# PortExpanderXRA1207_v2.net
KiCad netlist of a schematic drawn in EAGLE
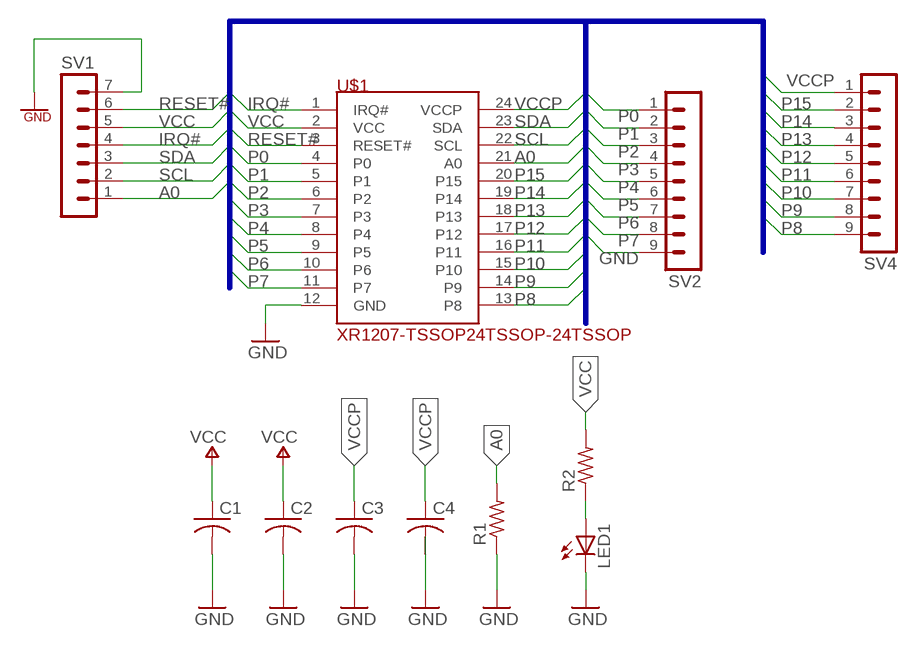
[diagram p0: schematic, sheet 1]

(export (version "E")
  (design (tool "Eeschema 10.0.6"))
  (components
    (comp (ref "C1")
      (value "C-USC1206")
      (footprint "eagle-import:C1206")
      (libsource (lib "eagle-import") (part "C-USC1206"))
    )
    (comp (ref "C2")
      (value "C-USC1206")
      (footprint "eagle-import:C1206")
      (libsource (lib "eagle-import") (part "C-USC1206"))
    )
    (comp (ref "C3")
      (value "C-USC1206")
      (footprint "eagle-import:C1206")
      (libsource (lib "eagle-import") (part "C-USC1206"))
    )
    (comp (ref "C4")
      (value "C-USC1206")
      (footprint "eagle-import:C1206")
      (libsource (lib "eagle-import") (part "C-USC1206"))
    )
    (comp (ref "LED1")
      (value "LEDSML0805")
      (footprint "eagle-import:SML0805")
      (libsource (lib "eagle-import") (part "LEDSML0805"))
    )
    (comp (ref "R1")
      (value "R-US_M1206")
      (footprint "eagle-import:M1206")
      (libsource (lib "eagle-import") (part "R-US_M1206"))
    )
    (comp (ref "R2")
      (value "R-US_M1206")
      (footprint "eagle-import:M1206")
      (libsource (lib "eagle-import") (part "R-US_M1206"))
    )
    (comp (ref "SV1")
      (value "MA07-1")
      (footprint "eagle-import:MA07-1")
      (libsource (lib "eagle-import") (part "MA07-1"))
    )
    (comp (ref "SV2")
      (value "MA09-1")
      (footprint "eagle-import:MA09-1")
      (libsource (lib "eagle-import") (part "MA09-1"))
    )
    (comp (ref "SV4")
      (value "MA09-1")
      (footprint "eagle-import:MA09-1")
      (libsource (lib "eagle-import") (part "MA09-1"))
    )
    (comp (ref "U$1")
      (value "XR1207-TSSOP24TSSOP-24TSSOP")
      (footprint "eagle-import:TSSOP-24")
      (libsource (lib "eagle-import") (part "XR1207-TSSOP24TSSOPTSSOP-24"))
    )
  )
  (nets
    (net (code "1") (name "/IRQ#") (class "Default")
      (node (ref "SV1") (pin "4") (pinfunction "4_4") (pintype "passive"))
      (node (ref "U$1") (pin "1") (pinfunction "IRQ#_1") (pintype "bidirectional"))
    )
    (net (code "2") (name "/P0") (class "Default")
      (node (ref "SV2") (pin "1") (pinfunction "1_1") (pintype "passive"))
      (node (ref "U$1") (pin "4") (pinfunction "P0_4") (pintype "bidirectional"))
    )
    (net (code "3") (name "/P1") (class "Default")
      (node (ref "SV2") (pin "2") (pinfunction "2_2") (pintype "passive"))
      (node (ref "U$1") (pin "5") (pinfunction "P1_5") (pintype "bidirectional"))
    )
    (net (code "4") (name "/P2") (class "Default")
      (node (ref "SV2") (pin "3") (pinfunction "3_3") (pintype "passive"))
      (node (ref "U$1") (pin "6") (pinfunction "P2_6") (pintype "bidirectional"))
    )
    (net (code "5") (name "/P3") (class "Default")
      (node (ref "SV2") (pin "4") (pinfunction "4_4") (pintype "passive"))
      (node (ref "U$1") (pin "7") (pinfunction "P3_7") (pintype "bidirectional"))
    )
    (net (code "6") (name "/P4") (class "Default")
      (node (ref "SV2") (pin "5") (pinfunction "5_5") (pintype "passive"))
      (node (ref "U$1") (pin "8") (pinfunction "P4_8") (pintype "bidirectional"))
    )
    (net (code "7") (name "/P5") (class "Default")
      (node (ref "SV2") (pin "6") (pinfunction "6_6") (pintype "passive"))
      (node (ref "U$1") (pin "9") (pinfunction "P5_9") (pintype "bidirectional"))
    )
    (net (code "8") (name "/P6") (class "Default")
      (node (ref "SV2") (pin "7") (pinfunction "7_7") (pintype "passive"))
      (node (ref "U$1") (pin "10") (pinfunction "P6_10") (pintype "bidirectional"))
    )
    (net (code "9") (name "/P7") (class "Default")
      (node (ref "SV2") (pin "8") (pinfunction "8_8") (pintype "passive"))
      (node (ref "U$1") (pin "11") (pinfunction "P7_11") (pintype "bidirectional"))
    )
    (net (code "10") (name "/P8") (class "Default")
      (node (ref "SV4") (pin "9") (pinfunction "9_9") (pintype "passive"))
      (node (ref "U$1") (pin "13") (pinfunction "P8_13") (pintype "bidirectional"))
    )
    (net (code "11") (name "/P9") (class "Default")
      (node (ref "SV4") (pin "8") (pinfunction "8_8") (pintype "passive"))
      (node (ref "U$1") (pin "14") (pinfunction "P9_14") (pintype "bidirectional"))
    )
    (net (code "12") (name "/P10") (class "Default")
      (node (ref "SV4") (pin "7") (pinfunction "7_7") (pintype "passive"))
      (node (ref "U$1") (pin "15") (pinfunction "P10_15") (pintype "bidirectional"))
    )
    (net (code "13") (name "/P11") (class "Default")
      (node (ref "SV4") (pin "6") (pinfunction "6_6") (pintype "passive"))
      (node (ref "U$1") (pin "16") (pinfunction "P11_16") (pintype "bidirectional"))
    )
    (net (code "14") (name "/P12") (class "Default")
      (node (ref "SV4") (pin "5") (pinfunction "5_5") (pintype "passive"))
      (node (ref "U$1") (pin "17") (pinfunction "P12_17") (pintype "bidirectional"))
    )
    (net (code "15") (name "/P13") (class "Default")
      (node (ref "SV4") (pin "4") (pinfunction "4_4") (pintype "passive"))
      (node (ref "U$1") (pin "18") (pinfunction "P13_18") (pintype "bidirectional"))
    )
    (net (code "16") (name "/P14") (class "Default")
      (node (ref "SV4") (pin "3") (pinfunction "3_3") (pintype "passive"))
      (node (ref "U$1") (pin "19") (pinfunction "P14_19") (pintype "bidirectional"))
    )
    (net (code "17") (name "/P15") (class "Default")
      (node (ref "SV4") (pin "2") (pinfunction "2_2") (pintype "passive"))
      (node (ref "U$1") (pin "20") (pinfunction "P15_20") (pintype "bidirectional"))
    )
    (net (code "18") (name "/RESET#") (class "Default")
      (node (ref "SV1") (pin "6") (pinfunction "6_6") (pintype "passive"))
      (node (ref "U$1") (pin "3") (pinfunction "RESET#_3") (pintype "bidirectional"))
    )
    (net (code "19") (name "/SCL") (class "Default")
      (node (ref "SV1") (pin "2") (pinfunction "2_2") (pintype "passive"))
      (node (ref "U$1") (pin "22") (pinfunction "SCL_22") (pintype "bidirectional"))
    )
    (net (code "20") (name "/SDA") (class "Default")
      (node (ref "SV1") (pin "3") (pinfunction "3_3") (pintype "passive"))
      (node (ref "U$1") (pin "23") (pinfunction "SDA_23") (pintype "bidirectional"))
    )
    (net (code "21") (name "A0") (class "Default")
      (node (ref "R1") (pin "2") (pinfunction "2_2") (pintype "passive"))
      (node (ref "SV1") (pin "1") (pinfunction "1_1") (pintype "passive"))
      (node (ref "U$1") (pin "21") (pinfunction "A0_21") (pintype "bidirectional"))
    )
    (net (code "22") (name "GND") (class "Default")
      (node (ref "C1") (pin "2") (pinfunction "2_2") (pintype "passive"))
      (node (ref "C2") (pin "2") (pinfunction "2_2") (pintype "passive"))
      (node (ref "C3") (pin "2") (pinfunction "2_2") (pintype "passive"))
      (node (ref "C4") (pin "2") (pinfunction "2_2") (pintype "passive"))
      (node (ref "LED1") (pin "C") (pinfunction "C_C") (pintype "passive"))
      (node (ref "R1") (pin "1") (pinfunction "1_1") (pintype "passive"))
      (node (ref "SV1") (pin "7") (pinfunction "7_7") (pintype "passive"))
      (node (ref "SV2") (pin "9") (pinfunction "9_9") (pintype "passive"))
      (node (ref "U$1") (pin "12") (pinfunction "GND_12") (pintype "bidirectional"))
    )
    (net (code "23") (name "Net-(LED1-PadA)") (class "Default")
      (node (ref "LED1") (pin "A") (pinfunction "A_A") (pintype "passive"))
      (node (ref "R2") (pin "1") (pinfunction "1_1") (pintype "passive"))
    )
    (net (code "24") (name "VCC") (class "Default")
      (node (ref "C1") (pin "1") (pinfunction "1_1") (pintype "passive"))
      (node (ref "C2") (pin "1") (pinfunction "1_1") (pintype "passive"))
      (node (ref "R2") (pin "2") (pinfunction "2_2") (pintype "passive"))
      (node (ref "SV1") (pin "5") (pinfunction "5_5") (pintype "passive"))
      (node (ref "U$1") (pin "2") (pinfunction "VCC_2") (pintype "bidirectional"))
    )
    (net (code "25") (name "VCCP") (class "Default")
      (node (ref "C3") (pin "1") (pinfunction "1_1") (pintype "passive"))
      (node (ref "C4") (pin "1") (pinfunction "1_1") (pintype "passive"))
      (node (ref "SV4") (pin "1") (pinfunction "1_1") (pintype "passive"))
      (node (ref "U$1") (pin "24") (pinfunction "VCCP_24") (pintype "bidirectional"))
    )
  )
)
